# current.net
KiCad netlist of a schematic drawn in EAGLE
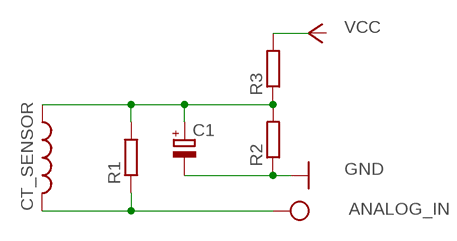
[diagram p0: schematic, sheet 1]

(export (version "E")
  (design (tool "Eeschema 10.0.6"))
  (components
    (comp (ref "C1")
      (value "CPOL-EUE2.5-6")
      (footprint "eagle-import:E2,5-6")
      (libsource (lib "eagle-import") (part "CPOL-EUE2.5-6"))
    )
    (comp (ref "CT_SENSOR")
      (value "L-USTJ9-U2")
      (footprint "eagle-import:TJ9-U2")
      (libsource (lib "eagle-import") (part "L-USTJ9-U2"))
    )
    (comp (ref "R1")
      (value "R-EU_0207/5V")
      (footprint "eagle-import:0207_5V")
      (libsource (lib "eagle-import") (part "R-EU_0207/5V"))
    )
    (comp (ref "R2")
      (value "R-EU_0207/5V")
      (footprint "eagle-import:0207_5V")
      (libsource (lib "eagle-import") (part "R-EU_0207/5V"))
    )
    (comp (ref "R3")
      (value "R-EU_0207/5V")
      (footprint "eagle-import:0207_5V")
      (libsource (lib "eagle-import") (part "R-EU_0207/5V"))
    )
  )
  (nets
    (net (code "1") (name "ANALOG_IN") (class "Default")
      (node (ref "CT_SENSOR") (pin "2") (pinfunction "2_2") (pintype "passive"))
      (node (ref "R1") (pin "1") (pinfunction "1_1") (pintype "passive"))
    )
    (net (code "2") (name "GND") (class "Default")
      (node (ref "C1") (pin "-") (pinfunction "-_-") (pintype "passive"))
      (node (ref "R2") (pin "1") (pinfunction "1_1") (pintype "passive"))
    )
    (net (code "3") (name "Net-(C1-Pad+)") (class "Default")
      (node (ref "C1") (pin "+") (pinfunction "+_+") (pintype "passive"))
      (node (ref "CT_SENSOR") (pin "1") (pinfunction "1_1") (pintype "passive"))
      (node (ref "R1") (pin "2") (pinfunction "2_2") (pintype "passive"))
      (node (ref "R2") (pin "2") (pinfunction "2_2") (pintype "passive"))
      (node (ref "R3") (pin "1") (pinfunction "1_1") (pintype "passive"))
    )
    (net (code "5") (name "unconnected-(R3-Pad2)") (class "Default")
      (node (ref "R3") (pin "2") (pinfunction "2_2") (pintype "passive"))
    )
  )
)
